# MCU_Power_Clock.net
KiCad netlist of a schematic drawn in Altium Designer
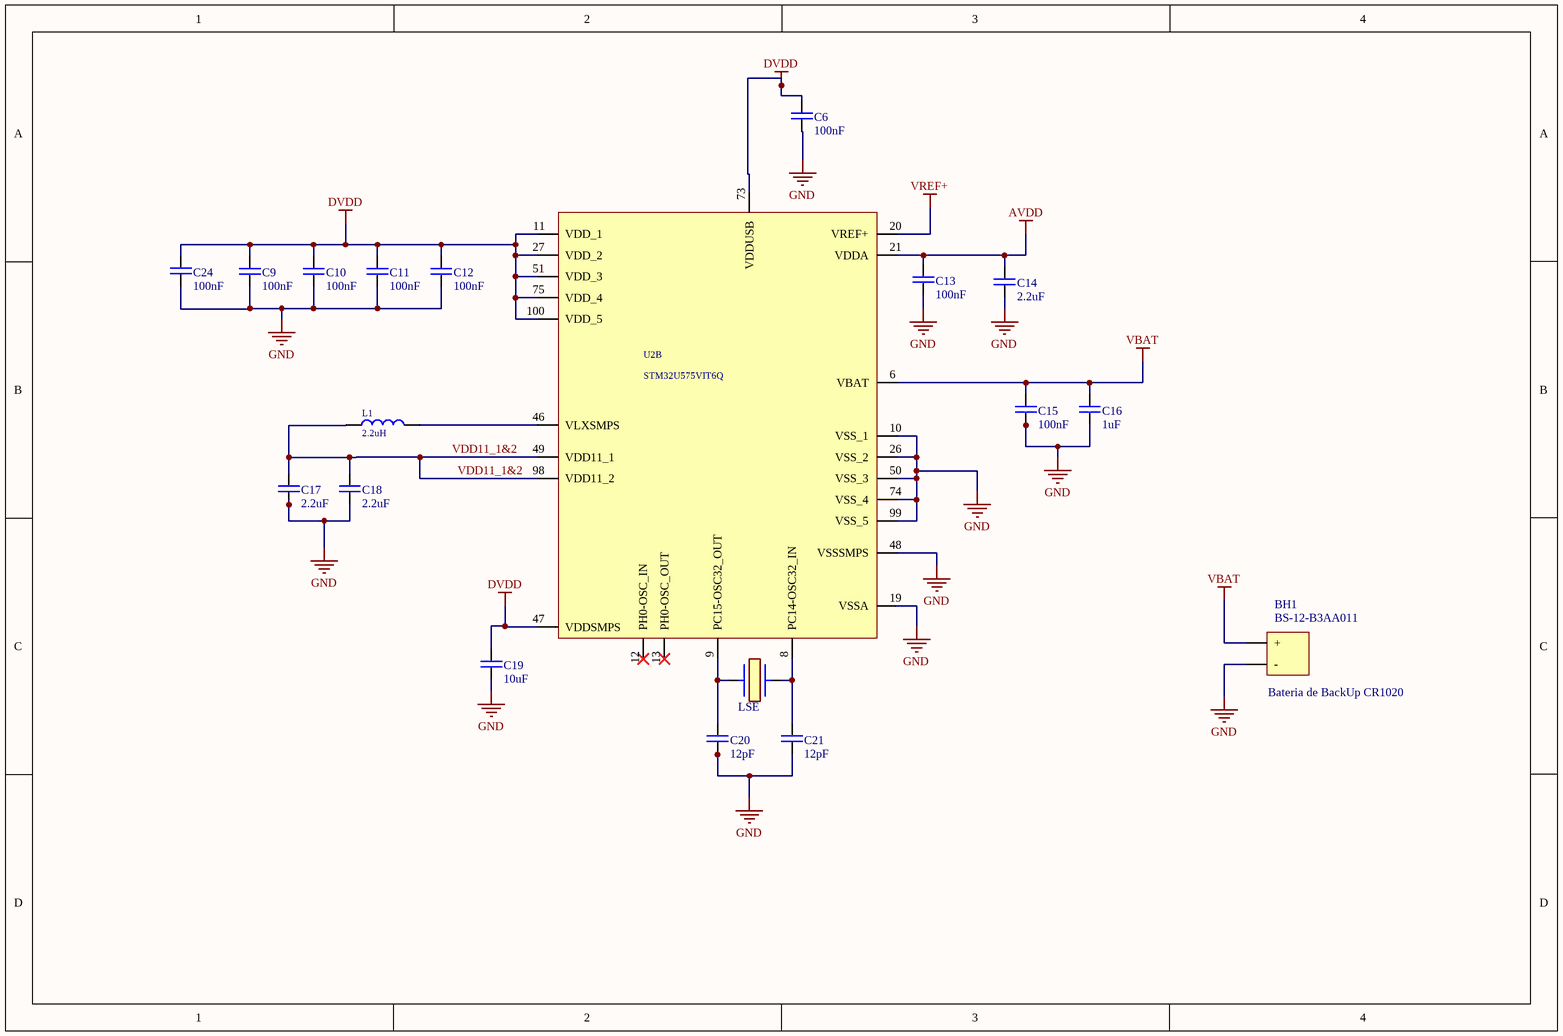
[diagram p0: MCU_Power_Clock.SchDoc]

(export (version "E")
  (design (tool "Eeschema 10.0.6"))
  (components
    (comp (ref "BH1")
      (value "BS-12-B3AA011")
      (footprint "BS-12-B3AA011")
      (description "Battery holder CR1020 SMD")
      (fields (field (name "MANUFACTURER") "Myoung"))
      (libsource (lib "flowmeet") (part "BS-12-B3AA011"))
    )
    (comp (ref "C6")
      (value "100nF")
      (footprint "CAP_SM0603_YAGEOCC2_N")
      (description "CAP 100nF SM0603 X7R 50V YAGEO CC2")
      (fields
        (field (name "MANUFACTURER") "Yageo")
        (field (name "MANUFACTURER PART NUMBER") "CC0603KRX7R9BB104")
      )
      (libsource (lib "yageo") (part "CC0603KRX7R9BB104"))
    )
    (comp (ref "C9")
      (value "100nF")
      (footprint "CAP_SM0603_YAGEOCC2_N")
      (description "CAP 100nF SM0603 X7R 50V YAGEO CC2")
      (fields
        (field (name "MANUFACTURER") "Yageo")
        (field (name "MANUFACTURER PART NUMBER") "CC0603KRX7R9BB104")
      )
      (libsource (lib "yageo") (part "CC0603KRX7R9BB104"))
    )
    (comp (ref "C10")
      (value "100nF")
      (footprint "CAP_SM0603_YAGEOCC2_N")
      (description "CAP 100nF SM0603 X7R 50V YAGEO CC2")
      (fields
        (field (name "MANUFACTURER") "Yageo")
        (field (name "MANUFACTURER PART NUMBER") "CC0603KRX7R9BB104")
      )
      (libsource (lib "yageo") (part "CC0603KRX7R9BB104"))
    )
    (comp (ref "C11")
      (value "100nF")
      (footprint "CAP_SM0603_YAGEOCC2_N")
      (description "CAP 100nF SM0603 X7R 50V YAGEO CC2")
      (fields
        (field (name "MANUFACTURER") "Yageo")
        (field (name "MANUFACTURER PART NUMBER") "CC0603KRX7R9BB104")
      )
      (libsource (lib "yageo") (part "CC0603KRX7R9BB104"))
    )
    (comp (ref "C12")
      (value "100nF")
      (footprint "CAP_SM0603_YAGEOCC2_N")
      (description "CAP 100nF SM0603 X7R 50V YAGEO CC2")
      (fields
        (field (name "MANUFACTURER") "Yageo")
        (field (name "MANUFACTURER PART NUMBER") "CC0603KRX7R9BB104")
      )
      (libsource (lib "yageo") (part "CC0603KRX7R9BB104"))
    )
    (comp (ref "C13")
      (value "100nF")
      (footprint "CAP_SM0603_YAGEOCC2_N")
      (description "CAP 100nF SM0603 X7R 50V YAGEO CC2")
      (fields
        (field (name "MANUFACTURER") "Yageo")
        (field (name "MANUFACTURER PART NUMBER") "CC0603KRX7R9BB104")
      )
      (libsource (lib "yageo") (part "CC0603KRX7R9BB104"))
    )
    (comp (ref "C14")
      (value "2.2uF")
      (footprint "CAP_SM0603_YAGEOCC2_N")
      (description "CAP 2.2uF (2u2F) SM0603 X7R 10V YAGEO CC2")
      (fields
        (field (name "MANUFACTURER") "Yageo")
        (field (name "MANUFACTURER PART NUMBER") "CC0603KRX7R6BB225")
      )
      (libsource (lib "yageo") (part "CC0603KRX7R6BB225"))
    )
    (comp (ref "C15")
      (value "100nF")
      (footprint "CAP_SM0603_YAGEOCC2_N")
      (description "CAP 100nF SM0603 X7R 50V YAGEO CC2")
      (fields
        (field (name "MANUFACTURER") "Yageo")
        (field (name "MANUFACTURER PART NUMBER") "CC0603KRX7R9BB104")
      )
      (libsource (lib "yageo") (part "CC0603KRX7R9BB104"))
    )
    (comp (ref "C16")
      (value "1uF")
      (footprint "CAP_SM0603_YAGEOCC2_N")
      (description "CAP 1uF SM0603 X7R 10V YAGEO CC2")
      (fields
        (field (name "MANUFACTURER") "Yageo")
        (field (name "MANUFACTURER PART NUMBER") "CC0603KRX7R6BB105")
      )
      (libsource (lib "yageo") (part "CC0603KRX7R6BB105"))
    )
    (comp (ref "C17")
      (value "2.2uF")
      (footprint "CAP_SM0603_YAGEOCC2_N")
      (description "CAP 2.2uF (2u2F) SM0603 X7R 10V YAGEO CC2")
      (fields
        (field (name "MANUFACTURER") "Yageo")
        (field (name "MANUFACTURER PART NUMBER") "CC0603KRX7R6BB225")
      )
      (libsource (lib "yageo") (part "CC0603KRX7R6BB225"))
    )
    (comp (ref "C18")
      (value "2.2uF")
      (footprint "CAP_SM0603_YAGEOCC2_N")
      (description "CAP 2.2uF (2u2F) SM0603 X7R 10V YAGEO CC2")
      (fields
        (field (name "MANUFACTURER") "Yageo")
        (field (name "MANUFACTURER PART NUMBER") "CC0603KRX7R6BB225")
      )
      (libsource (lib "yageo") (part "CC0603KRX7R6BB225"))
    )
    (comp (ref "C19")
      (value "10uF")
      (footprint "CAP_SM0603_YAGEOCC2_N")
      (description "CAP 10uF SM0603 X5R 10V YAGEO")
      (fields
        (field (name "MANUFACTURER") "Yageo")
        (field (name "MANUFACTURER PART NUMBER") "CC0603KRX5R6BB106")
      )
      (libsource (lib "yageo") (part "CC0603KRX5R6BB106"))
    )
    (comp (ref "C20")
      (value "12pF")
      (footprint "CAP_SM0603_YAGEOCC2_N")
      (description "CAP 12pF SM0603 NPO 50V YAGEO CC2")
      (fields
        (field (name "MANUFACTURER") "Yageo")
        (field (name "MANUFACTURER PART NUMBER") "CC0603JRNPO9BN120")
      )
      (libsource (lib "yageo") (part "CC0603JRNPO9BN120"))
    )
    (comp (ref "C21")
      (value "12pF")
      (footprint "CAP_SM0603_YAGEOCC2_N")
      (description "CAP 12pF SM0603 NPO 50V YAGEO CC2")
      (fields
        (field (name "MANUFACTURER") "Yageo")
        (field (name "MANUFACTURER PART NUMBER") "CC0603JRNPO9BN120")
      )
      (libsource (lib "yageo") (part "CC0603JRNPO9BN120"))
    )
    (comp (ref "C24")
      (value "100nF")
      (footprint "CAP_SM0603_YAGEOCC2_N")
      (description "CAP 100nF SM0603 X7R 50V YAGEO CC2")
      (fields
        (field (name "MANUFACTURER") "Yageo")
        (field (name "MANUFACTURER PART NUMBER") "CC0603KRX7R9BB104")
      )
      (libsource (lib "yageo") (part "CC0603KRX7R9BB104"))
    )
    (comp (ref "L1")
      (value "2.2uH")
      (footprint "LQM21PN2R2MGHL")
      (description "Inductores de potencia - SMD 2.2 UH 20%")
      (fields
        (field (name "MANUFACTURER") "Murata Electronics")
        (field (name "MANUFACTURER PART NUMBER") "LQM21PN2R2MGHL")
      )
      (libsource (lib "Inductores") (part "LQM21PN2R2MGHL"))
    )
    (comp (ref "LSE")
      (value "32,768 kHz")
      (footprint "SC-32S32.768kHz20PPM12.5pF")
      (description "Cristal Oscilador 32.768 kHz, 12.5pF")
      (fields
        (field (name "MANUFACTURER") "Seiko")
        (field (name "MANUFACTURER PART NUMBER") "SC32S-12.5PF20PPM")
      )
      (libsource (lib "Osciladores") (part "SC32S-12.5PF20PPM"))
    )
    (comp (ref "U2")
      (value "STM32U575VIT6Q")
      (footprint "STM32U575VI")
      (fields (field (name "MANUFACTURER") "ST"))
      (libsource (lib "flowmeet") (part "STM32U575VIT6Q"))
    )
  )
  (nets
    (net (code "1") (name "/VDD11_1&2") (class "Default")
      (node (ref "C17") (pin "1") (pintype "passive"))
      (node (ref "C18") (pin "1") (pintype "passive"))
      (node (ref "L1") (pin "1") (pinfunction "1_1") (pintype "passive"))
      (node (ref "U2") (pin "49") (pinfunction "VDD11_1_49") (pintype "passive"))
      (node (ref "U2") (pin "98") (pinfunction "VDD11_2_98") (pintype "passive"))
    )
    (net (code "2") (name "AVDD") (class "Default")
      (node (ref "C13") (pin "1") (pintype "passive"))
      (node (ref "C14") (pin "1") (pintype "passive"))
      (node (ref "U2") (pin "21") (pinfunction "VDDA_21") (pintype "passive"))
    )
    (net (code "3") (name "DVDD") (class "Default")
      (node (ref "C10") (pin "1") (pintype "passive"))
      (node (ref "C11") (pin "1") (pintype "passive"))
      (node (ref "C12") (pin "1") (pintype "passive"))
      (node (ref "C19") (pin "1") (pintype "passive"))
      (node (ref "C24") (pin "1") (pintype "passive"))
      (node (ref "C6") (pin "1") (pintype "passive"))
      (node (ref "C9") (pin "1") (pintype "passive"))
      (node (ref "U2") (pin "100") (pinfunction "VDD_5_100") (pintype "passive"))
      (node (ref "U2") (pin "11") (pinfunction "VDD_1_11") (pintype "passive"))
      (node (ref "U2") (pin "27") (pinfunction "VDD_2_27") (pintype "passive"))
      (node (ref "U2") (pin "47") (pinfunction "VDDSMPS_47") (pintype "passive"))
      (node (ref "U2") (pin "51") (pinfunction "VDD_3_51") (pintype "passive"))
      (node (ref "U2") (pin "73") (pinfunction "VDDUSB_73") (pintype "passive"))
      (node (ref "U2") (pin "75") (pinfunction "VDD_4_75") (pintype "passive"))
    )
    (net (code "4") (name "GND") (class "Default")
      (node (ref "BH1") (pin "NEG") (pinfunction "-_NEG") (pintype "passive"))
      (node (ref "C10") (pin "2") (pintype "passive"))
      (node (ref "C11") (pin "2") (pintype "passive"))
      (node (ref "C12") (pin "2") (pintype "passive"))
      (node (ref "C13") (pin "2") (pintype "passive"))
      (node (ref "C14") (pin "2") (pintype "passive"))
      (node (ref "C15") (pin "2") (pintype "passive"))
      (node (ref "C16") (pin "2") (pintype "passive"))
      (node (ref "C17") (pin "2") (pintype "passive"))
      (node (ref "C18") (pin "2") (pintype "passive"))
      (node (ref "C19") (pin "2") (pintype "passive"))
      (node (ref "C20") (pin "2") (pintype "passive"))
      (node (ref "C21") (pin "2") (pintype "passive"))
      (node (ref "C24") (pin "2") (pintype "passive"))
      (node (ref "C6") (pin "2") (pintype "passive"))
      (node (ref "C9") (pin "2") (pintype "passive"))
      (node (ref "U2") (pin "10") (pinfunction "VSS_1_10") (pintype "passive"))
      (node (ref "U2") (pin "19") (pinfunction "VSSA_19") (pintype "passive"))
      (node (ref "U2") (pin "26") (pinfunction "VSS_2_26") (pintype "passive"))
      (node (ref "U2") (pin "48") (pinfunction "VSSSMPS_48") (pintype "passive"))
      (node (ref "U2") (pin "50") (pinfunction "VSS_3_50") (pintype "passive"))
      (node (ref "U2") (pin "74") (pinfunction "VSS_4_74") (pintype "passive"))
      (node (ref "U2") (pin "99") (pinfunction "VSS_5_99") (pintype "passive"))
    )
    (net (code "5") (name "Net-(U2B-PC14-OSC32_IN)") (class "Default")
      (node (ref "C21") (pin "1") (pintype "passive"))
      (node (ref "LSE") (pin "2") (pinfunction "2_2") (pintype "passive"))
      (node (ref "U2") (pin "8") (pinfunction "PC14-OSC32_IN_8") (pintype "passive"))
    )
    (net (code "6") (name "Net-(U2B-PC15-OSC32_OUT)") (class "Default")
      (node (ref "C20") (pin "1") (pintype "passive"))
      (node (ref "LSE") (pin "1") (pinfunction "1_1") (pintype "passive"))
      (node (ref "U2") (pin "9") (pinfunction "PC15-OSC32_OUT_9") (pintype "passive"))
    )
    (net (code "7") (name "Net-(U2B-VLXSMPS)") (class "Default")
      (node (ref "L1") (pin "2") (pinfunction "2_2") (pintype "passive"))
      (node (ref "U2") (pin "46") (pinfunction "VLXSMPS_46") (pintype "passive"))
    )
    (net (code "8") (name "VBAT") (class "Default")
      (node (ref "BH1") (pin "POS") (pinfunction "+_POS") (pintype "passive"))
      (node (ref "C15") (pin "1") (pintype "passive"))
      (node (ref "C16") (pin "1") (pintype "passive"))
      (node (ref "U2") (pin "6") (pinfunction "VBAT_6") (pintype "passive"))
    )
    (net (code "9") (name "VREF+") (class "Default")
      (node (ref "U2") (pin "20") (pinfunction "VREF+_20") (pintype "passive"))
    )
    (net (code "10") (name "unconnected-(U2B-PH0-OSC_IN-Pad12)") (class "Default")
      (node (ref "U2") (pin "12") (pinfunction "PH0-OSC_IN_12") (pintype "passive+no_connect"))
    )
    (net (code "11") (name "unconnected-(U2B-PH0-OSC_OUT-Pad13)") (class "Default")
      (node (ref "U2") (pin "13") (pinfunction "PH0-OSC_OUT_13") (pintype "passive+no_connect"))
    )
  )
)
